# Programacion_ICSP.net
KiCad netlist of a schematic drawn in Altium Designer
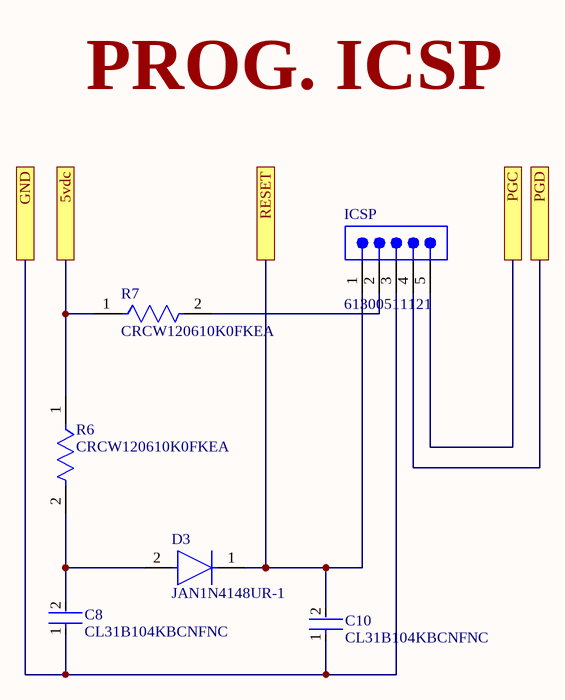
[diagram p0: Programacion ICSP.SchDoc]

(export (version "E")
  (design (tool "Eeschema 10.0.6"))
  (components
    (comp (ref "C8")
      (value "CL31B104KBCNFNC")
      (footprint "FP-CL31-IPC_C")
      (description "Cap Ceramic 100nF 50V X7R ±10% SMD 1206 +125°C Embossed T/R")
      (fields (field (name "TOLERANCE") "10%"))
      (libsource (lib "Altium Content Vault") (part "b4654b650e69147ec39a6b967a45e02"))
    )
    (comp (ref "C10")
      (value "CL31B104KBCNFNC")
      (footprint "FP-CL31-IPC_C")
      (description "Cap Ceramic 100nF 50V X7R ±10% SMD 1206 +125°C Embossed T/R")
      (fields (field (name "TOLERANCE") "10%"))
      (libsource (lib "Altium Content Vault") (part "b4654b650e69147ec39a6b967a45e02"))
    )
    (comp (ref "D3")
      (value "JAN1N4148UR-1")
      (footprint "FP-DO-213AA-MFG")
      (description "DIODE GEN PURP 100V 200MA DO213")
      (libsource (lib "Altium Content Vault") (part "d7152d700b627762746794eb795d46e"))
    )
    (comp (ref "ICSP")
      (value "61300511121")
      (footprint "61300511121")
      (libsource (lib "Altium Content Vault") (part "Header_Male_1R_05P"))
    )
    (comp (ref "R6")
      (value "CRCW120610K0FKEA")
      (footprint "FP-CRCW1206-e3-IPC_C")
      (description "RES Thick Film, 10kΩ, 1%, 0.25W, 100ppm/°C, 1206")
      (fields (field (name "TOLERANCE") "1%"))
      (libsource (lib "Altium Content Vault") (part "1029c3af85768c4190bb7ad29bc67b5"))
    )
    (comp (ref "R7")
      (value "CRCW120610K0FKEA")
      (footprint "FP-CRCW1206-e3-IPC_C")
      (description "RES Thick Film, 10kΩ, 1%, 0.25W, 100ppm/°C, 1206")
      (fields (field (name "TOLERANCE") "1%"))
      (libsource (lib "Altium Content Vault") (part "1029c3af85768c4190bb7ad29bc67b5"))
    )
  )
  (nets
    (net (code "1") (name "/5vdc") (class "Default")
      (node (ref "R6") (pin "1") (pinfunction "1_1") (pintype "passive"))
      (node (ref "R7") (pin "1") (pinfunction "1_1") (pintype "passive"))
    )
    (net (code "2") (name "/GND") (class "Default")
      (node (ref "C10") (pin "1") (pinfunction "1_1") (pintype "passive"))
      (node (ref "C8") (pin "1") (pinfunction "1_1") (pintype "passive"))
      (node (ref "ICSP") (pin "3") (pinfunction "3_3") (pintype "passive"))
    )
    (net (code "3") (name "/PGC") (class "Default")
      (node (ref "ICSP") (pin "5") (pinfunction "5_5") (pintype "passive"))
    )
    (net (code "4") (name "/PGD") (class "Default")
      (node (ref "ICSP") (pin "4") (pinfunction "4_4") (pintype "passive"))
    )
    (net (code "5") (name "/RESET") (class "Default")
      (node (ref "C10") (pin "2") (pinfunction "2_2") (pintype "passive"))
      (node (ref "D3") (pin "1") (pinfunction "C_1") (pintype "passive"))
      (node (ref "ICSP") (pin "1") (pinfunction "1_1") (pintype "passive"))
    )
    (net (code "6") (name "Net-(D3-A)") (class "Default")
      (node (ref "C8") (pin "2") (pinfunction "2_2") (pintype "passive"))
      (node (ref "D3") (pin "2") (pinfunction "A_2") (pintype "passive"))
      (node (ref "R6") (pin "2") (pinfunction "2_2") (pintype "passive"))
    )
    (net (code "7") (name "Net-(ICSP-Pad2)") (class "Default")
      (node (ref "ICSP") (pin "2") (pinfunction "2_2") (pintype "passive"))
      (node (ref "R7") (pin "2") (pinfunction "2_2") (pintype "passive"))
    )
  )
)
